# TLM_002_CONNECT.net
KiCad netlist of a schematic drawn in Altium Designer
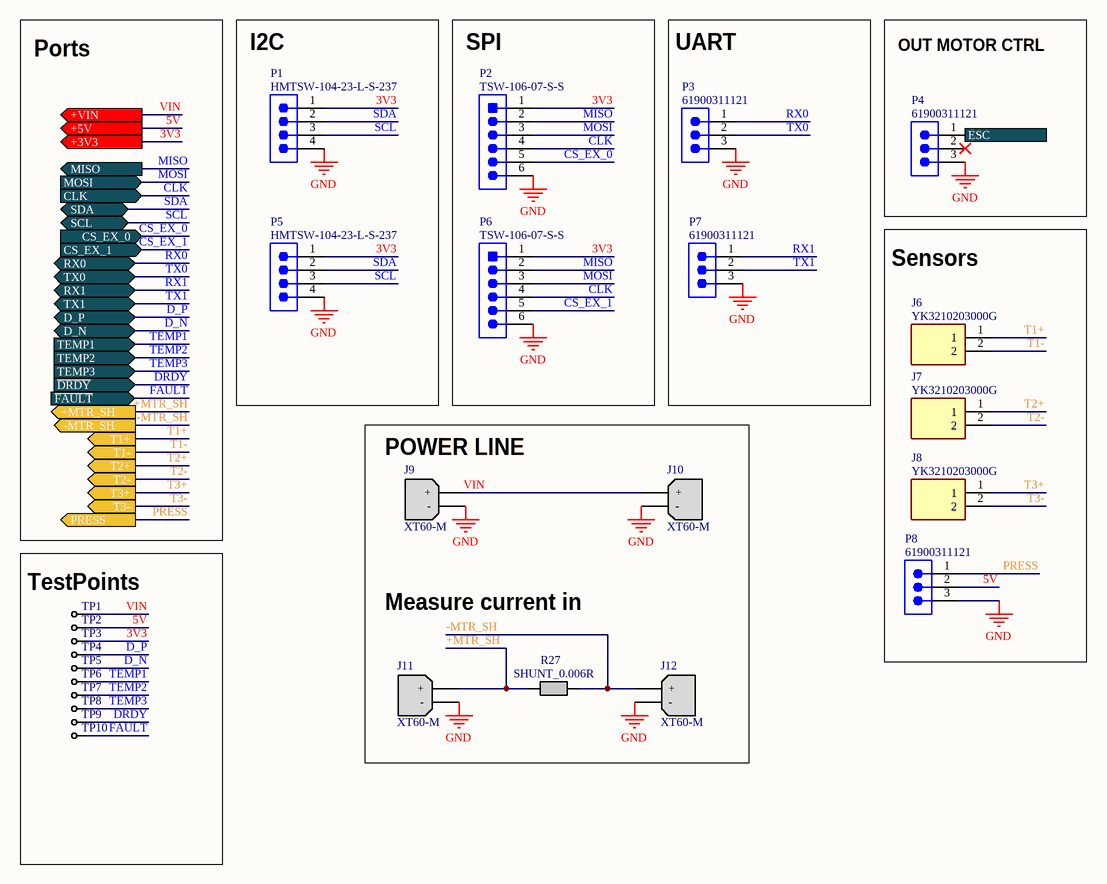
[diagram p0: TLM_002_CONNECT.SchDoc]

(export (version "E")
  (design (tool "Eeschema 10.0.6"))
  (components
    (comp (ref "J6")
      (value "YK3210203000G")
      (footprint "SamacSys:YK3210203000G")
      (description "Connector")
      (fields (field (name "MOUSER PART NUMBER") "649-YK32102030J0G"))
      (libsource (lib "*") (part "YK3210203000G"))
    )
    (comp (ref "J7")
      (value "YK3210203000G")
      (footprint "SamacSys:YK3210203000G")
      (description "Connector")
      (fields (field (name "MOUSER PART NUMBER") "649-YK32102030J0G"))
      (libsource (lib "*") (part "YK3210203000G"))
    )
    (comp (ref "J8")
      (value "YK3210203000G")
      (footprint "SamacSys:YK3210203000G")
      (description "Connector")
      (fields (field (name "MOUSER PART NUMBER") "649-YK32102030J0G"))
      (libsource (lib "*") (part "YK3210203000G"))
    )
    (comp (ref "J9")
      (value "XT60-M")
      (footprint "AMASS_XT60-M")
      (description "Plug; DC supply; XT60; male; PIN: 2; for cable; soldered; 30A; 500V")
      (fields (field (name "MF") "AMASS"))
      (libsource (lib "XT60-M") (part "XT60-M"))
    )
    (comp (ref "J10")
      (value "XT60-M")
      (footprint "AMASS_XT60-M")
      (description "Plug; DC supply; XT60; male; PIN: 2; for cable; soldered; 30A; 500V")
      (fields (field (name "MF") "AMASS"))
      (libsource (lib "XT60-M") (part "XT60-M"))
    )
    (comp (ref "J11")
      (value "XT60-M")
      (footprint "AMASS_XT60-M")
      (description "Plug; DC supply; XT60; male; PIN: 2; for cable; soldered; 30A; 500V")
      (fields (field (name "MF") "AMASS"))
      (libsource (lib "XT60-M") (part "XT60-M"))
    )
    (comp (ref "J12")
      (value "XT60-M")
      (footprint "AMASS_XT60-M")
      (description "Plug; DC supply; XT60; male; PIN: 2; for cable; soldered; 30A; 500V")
      (fields (field (name "MF") "AMASS"))
      (libsource (lib "XT60-M") (part "XT60-M"))
    )
    (comp (ref "P1")
      (value "HMTSW-104-23-L-S-237")
      (footprint "SMTC-HMTSW-104-23-X-S-237")
      (fields (field (name "MANUFACTURER") "Samtec"))
      (libsource (lib "Altium Content Vault") (part "SMTC-HMTSW-104-23-X-S-237"))
    )
    (comp (ref "P2")
      (value "TSW-106-07-S-S")
      (footprint "SMTC-TSW-106-07-S-S_V")
      (fields (field (name "MANUFACTURER") "Samtec"))
      (libsource (lib "Altium Content Vault") (part "CN-1P-M-R6"))
    )
    (comp (ref "P3")
      (value "61900311121")
      (footprint "61900311121")
      (libsource (lib "Altium Content Vault") (part "Header_Male_1R_03P"))
    )
    (comp (ref "P4")
      (value "61900311121")
      (footprint "61900311121")
      (libsource (lib "Altium Content Vault") (part "Header_Male_1R_03P"))
    )
    (comp (ref "P5")
      (value "HMTSW-104-23-L-S-237")
      (footprint "SMTC-HMTSW-104-23-X-S-237")
      (fields (field (name "MANUFACTURER") "Samtec"))
      (libsource (lib "Altium Content Vault") (part "SMTC-HMTSW-104-23-X-S-237"))
    )
    (comp (ref "P6")
      (value "TSW-106-07-S-S")
      (footprint "SMTC-TSW-106-07-S-S_V")
      (fields (field (name "MANUFACTURER") "Samtec"))
      (libsource (lib "Altium Content Vault") (part "CN-1P-M-R6"))
    )
    (comp (ref "P7")
      (value "61900311121")
      (footprint "61900311121")
      (libsource (lib "Altium Content Vault") (part "Header_Male_1R_03P"))
    )
    (comp (ref "P8")
      (value "61900311121")
      (footprint "61900311121")
      (libsource (lib "Altium Content Vault") (part "Header_Male_1R_03P"))
    )
    (comp (ref "R27")
      (value "SHUNT_0.006R")
      (footprint "SHUNT")
      (libsource (lib "Generic-Schematic-Library") (part "SHUNT_0.006R"))
    )
    (comp (ref "TP1")
      (value "TestPoint")
      (footprint "TestPoint")
      (libsource (lib "Generic-Schematic-Library") (part "TestPoint"))
    )
    (comp (ref "TP2")
      (value "TestPoint")
      (footprint "TestPoint")
      (libsource (lib "Generic-Schematic-Library") (part "TestPoint"))
    )
    (comp (ref "TP3")
      (value "TestPoint")
      (footprint "TestPoint")
      (libsource (lib "Generic-Schematic-Library") (part "TestPoint"))
    )
    (comp (ref "TP4")
      (value "TestPoint")
      (footprint "TestPoint")
      (libsource (lib "Generic-Schematic-Library") (part "TestPoint"))
    )
    (comp (ref "TP5")
      (value "TestPoint")
      (footprint "TestPoint")
      (libsource (lib "Generic-Schematic-Library") (part "TestPoint"))
    )
    (comp (ref "TP6")
      (value "TestPoint")
      (footprint "TestPoint")
      (libsource (lib "Generic-Schematic-Library") (part "TestPoint"))
    )
    (comp (ref "TP7")
      (value "TestPoint")
      (footprint "TestPoint")
      (libsource (lib "Generic-Schematic-Library") (part "TestPoint"))
    )
    (comp (ref "TP8")
      (value "TestPoint")
      (footprint "TestPoint")
      (libsource (lib "Generic-Schematic-Library") (part "TestPoint"))
    )
    (comp (ref "TP9")
      (value "TestPoint")
      (footprint "TestPoint")
      (libsource (lib "Generic-Schematic-Library") (part "TestPoint"))
    )
    (comp (ref "TP10")
      (value "TestPoint")
      (footprint "TestPoint")
      (libsource (lib "Generic-Schematic-Library") (part "TestPoint"))
    )
  )
  (nets
    (net (code "1") (name "/+MTR_SH") (class "Default")
      (node (ref "J11") (pin "1") (pinfunction "+_1") (pintype "passive"))
      (node (ref "R27") (pin "1") (pinfunction "1_1") (pintype "passive"))
    )
    (net (code "2") (name "/-MTR_SH") (class "Default")
      (node (ref "J12") (pin "1") (pinfunction "+_1") (pintype "passive"))
      (node (ref "R27") (pin "2") (pinfunction "2_2") (pintype "passive"))
    )
    (net (code "3") (name "/3V3") (class "Default")
      (node (ref "P1") (pin "1") (pinfunction "1_1") (pintype "passive"))
      (node (ref "P2") (pin "1") (pinfunction "1_1") (pintype "passive"))
      (node (ref "P5") (pin "1") (pinfunction "1_1") (pintype "passive"))
      (node (ref "P6") (pin "1") (pinfunction "1_1") (pintype "passive"))
      (node (ref "TP3") (pin "1") (pinfunction "1_1") (pintype "passive"))
    )
    (net (code "4") (name "/5V") (class "Default")
      (node (ref "P8") (pin "2") (pinfunction "2_2") (pintype "passive"))
      (node (ref "TP2") (pin "1") (pinfunction "1_1") (pintype "passive"))
    )
    (net (code "5") (name "/CLK") (class "Default")
      (node (ref "P2") (pin "4") (pinfunction "4_4") (pintype "passive"))
      (node (ref "P6") (pin "4") (pinfunction "4_4") (pintype "passive"))
    )
    (net (code "6") (name "/CS_EX_0") (class "Default")
      (node (ref "P2") (pin "5") (pinfunction "5_5") (pintype "passive"))
    )
    (net (code "7") (name "/CS_EX_1") (class "Default")
      (node (ref "P6") (pin "5") (pinfunction "5_5") (pintype "passive"))
    )
    (net (code "8") (name "/D_N") (class "Default")
      (node (ref "TP5") (pin "1") (pinfunction "1_1") (pintype "passive"))
    )
    (net (code "9") (name "/D_P") (class "Default")
      (node (ref "TP4") (pin "1") (pinfunction "1_1") (pintype "passive"))
    )
    (net (code "10") (name "/ESC") (class "Default")
      (node (ref "P4") (pin "1") (pinfunction "1_1") (pintype "passive"))
    )
    (net (code "11") (name "/MISO") (class "Default")
      (node (ref "P2") (pin "2") (pinfunction "2_2") (pintype "passive"))
      (node (ref "P6") (pin "2") (pinfunction "2_2") (pintype "passive"))
    )
    (net (code "12") (name "/MOSI") (class "Default")
      (node (ref "P2") (pin "3") (pinfunction "3_3") (pintype "passive"))
      (node (ref "P6") (pin "3") (pinfunction "3_3") (pintype "passive"))
    )
    (net (code "13") (name "/PRESS") (class "Default")
      (node (ref "P8") (pin "1") (pinfunction "1_1") (pintype "passive"))
    )
    (net (code "14") (name "/RX0") (class "Default")
      (node (ref "P3") (pin "1") (pinfunction "1_1") (pintype "passive"))
    )
    (net (code "15") (name "/RX1") (class "Default")
      (node (ref "P7") (pin "1") (pinfunction "1_1") (pintype "passive"))
    )
    (net (code "16") (name "/SCL") (class "Default")
      (node (ref "P1") (pin "3") (pinfunction "3_3") (pintype "passive"))
      (node (ref "P5") (pin "3") (pinfunction "3_3") (pintype "passive"))
    )
    (net (code "17") (name "/SDA") (class "Default")
      (node (ref "P1") (pin "2") (pinfunction "2_2") (pintype "passive"))
      (node (ref "P5") (pin "2") (pinfunction "2_2") (pintype "passive"))
    )
    (net (code "18") (name "/T1+") (class "Default")
      (node (ref "J6") (pin "1") (pinfunction "1_1") (pintype "passive"))
    )
    (net (code "19") (name "/T1-") (class "Default")
      (node (ref "J6") (pin "2") (pinfunction "2_2") (pintype "passive"))
    )
    (net (code "20") (name "/T2+") (class "Default")
      (node (ref "J7") (pin "1") (pinfunction "1_1") (pintype "passive"))
    )
    (net (code "21") (name "/T2-") (class "Default")
      (node (ref "J7") (pin "2") (pinfunction "2_2") (pintype "passive"))
    )
    (net (code "22") (name "/T3+") (class "Default")
      (node (ref "J8") (pin "1") (pinfunction "1_1") (pintype "passive"))
    )
    (net (code "23") (name "/T3-") (class "Default")
      (node (ref "J8") (pin "2") (pinfunction "2_2") (pintype "passive"))
    )
    (net (code "24") (name "/TEMP1") (class "Default")
      (node (ref "TP6") (pin "1") (pinfunction "1_1") (pintype "passive"))
    )
    (net (code "25") (name "/TEMP2") (class "Default")
      (node (ref "TP7") (pin "1") (pinfunction "1_1") (pintype "passive"))
    )
    (net (code "26") (name "/TEMP3") (class "Default")
      (node (ref "TP8") (pin "1") (pinfunction "1_1") (pintype "passive"))
    )
    (net (code "27") (name "/TX0") (class "Default")
      (node (ref "P3") (pin "2") (pinfunction "2_2") (pintype "passive"))
    )
    (net (code "28") (name "/TX1") (class "Default")
      (node (ref "P7") (pin "2") (pinfunction "2_2") (pintype "passive"))
    )
    (net (code "29") (name "/VIN") (class "Default")
      (node (ref "J10") (pin "1") (pinfunction "+_1") (pintype "passive"))
      (node (ref "J9") (pin "1") (pinfunction "+_1") (pintype "passive"))
      (node (ref "TP1") (pin "1") (pinfunction "1_1") (pintype "passive"))
    )
    (net (code "30") (name "/~{DRDY}") (class "Default")
      (node (ref "TP9") (pin "1") (pinfunction "1_1") (pintype "passive"))
    )
    (net (code "31") (name "/~{FAULT}") (class "Default")
      (node (ref "TP10") (pin "1") (pinfunction "1_1") (pintype "passive"))
    )
    (net (code "32") (name "GND") (class "Default")
      (node (ref "J10") (pin "2") (pinfunction "-_2") (pintype "passive"))
      (node (ref "J11") (pin "2") (pinfunction "-_2") (pintype "passive"))
      (node (ref "J12") (pin "2") (pinfunction "-_2") (pintype "passive"))
      (node (ref "J9") (pin "2") (pinfunction "-_2") (pintype "passive"))
      (node (ref "P1") (pin "4") (pinfunction "4_4") (pintype "passive"))
      (node (ref "P2") (pin "6") (pinfunction "6_6") (pintype "passive"))
      (node (ref "P3") (pin "3") (pinfunction "3_3") (pintype "passive"))
      (node (ref "P4") (pin "3") (pinfunction "3_3") (pintype "passive"))
      (node (ref "P5") (pin "4") (pinfunction "4_4") (pintype "passive"))
      (node (ref "P6") (pin "6") (pinfunction "6_6") (pintype "passive"))
      (node (ref "P7") (pin "3") (pinfunction "3_3") (pintype "passive"))
      (node (ref "P8") (pin "3") (pinfunction "3_3") (pintype "passive"))
    )
    (net (code "33") (name "unconnected-(P4-Pad2)") (class "Default")
      (node (ref "P4") (pin "2") (pinfunction "2_2") (pintype "passive+no_connect"))
    )
  )
)
